# arduino_shield_drumline.net
KiCad netlist of a schematic drawn in EAGLE
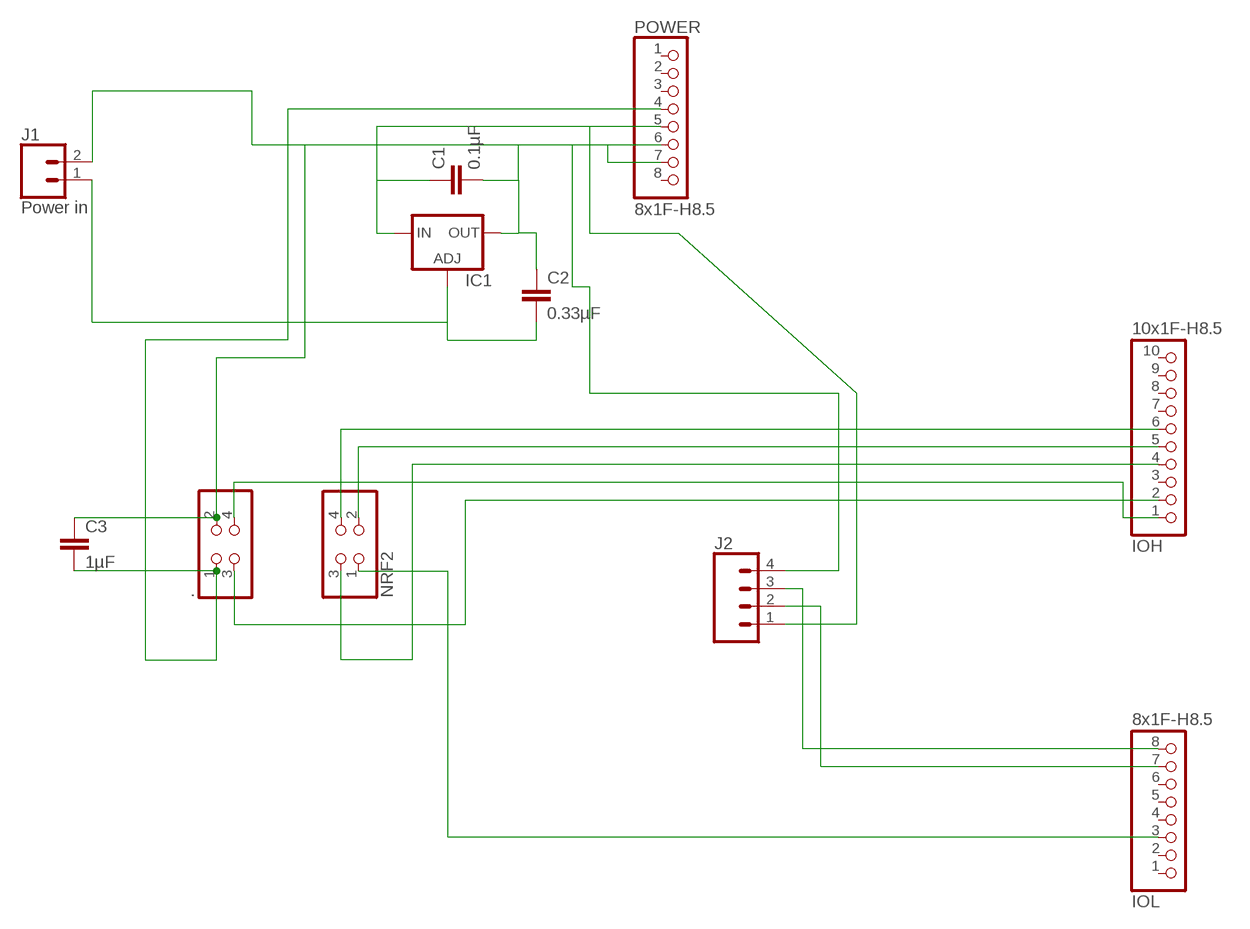
[diagram p0: schematic, sheet 1]

(export (version "E")
  (design (tool "Eeschema 10.0.6"))
  (components
    (comp (ref ".")
      (value "PINHD-2X2")
      (footprint "eagle-import:2X02")
      (libsource (lib "eagle-import") (part "PINHD-2X2"))
    )
    (comp (ref "C1")
      (value "0.1µF")
      (footprint "eagle-import:0805")
      (libsource (lib "eagle-import") (part "0.33UF/330NF-0805-50V-10%"))
    )
    (comp (ref "C2")
      (value "0.33µF")
      (footprint "eagle-import:0805")
      (libsource (lib "eagle-import") (part "0.33UF/330NF-0805-50V-10%"))
    )
    (comp (ref "C3")
      (value "1µF")
      (footprint "eagle-import:0805")
      (libsource (lib "eagle-import") (part "0.33UF/330NF-0805-50V-10%"))
    )
    (comp (ref "IC1")
      (value "LM138-TS")
      (footprint "eagle-import:TO220S")
      (libsource (lib "eagle-import") (part "LM138-TS"))
    )
    (comp (ref "IOH")
      (value "10x1F-H8.5")
      (footprint "eagle-import:1X10")
      (libsource (lib "eagle-import") (part "PINHD-1X10_ARD"))
    )
    (comp (ref "IOL")
      (value "8x1F-H8.5")
      (footprint "eagle-import:1X08")
      (libsource (lib "eagle-import") (part "PINHD-1X8"))
    )
    (comp (ref "J1")
      (value "Power in")
      (footprint "eagle-import:1X02")
      (libsource (lib "eagle-import") (part "CONN_02"))
    )
    (comp (ref "J2")
      (value "CONN_04")
      (footprint "eagle-import:1X04")
      (libsource (lib "eagle-import") (part "CONN_04"))
    )
    (comp (ref "NRF2")
      (value "PINHD-2X2")
      (footprint "eagle-import:2X02")
      (libsource (lib "eagle-import") (part "PINHD-2X2"))
    )
    (comp (ref "POWER")
      (value "8x1F-H8.5")
      (footprint "eagle-import:1X08")
      (libsource (lib "eagle-import") (part "PINHD-1X8"))
    )
  )
  (nets
    (net (code "1") (name "Net-(.-Pad1)") (class "Default")
      (node (ref ".") (pin "1") (pinfunction "1_1") (pintype "passive"))
      (node (ref "C3") (pin "2") (pinfunction "2_2") (pintype "passive"))
      (node (ref "POWER") (pin "4") (pinfunction "4_4") (pintype "passive"))
    )
    (net (code "2") (name "Net-(.-Pad3)") (class "Default")
      (node (ref ".") (pin "3") (pinfunction "3_3") (pintype "passive"))
      (node (ref "IOH") (pin "2") (pinfunction "2_2") (pintype "passive"))
    )
    (net (code "3") (name "Net-(.-Pad4)") (class "Default")
      (node (ref ".") (pin "4") (pinfunction "4_4") (pintype "passive"))
      (node (ref "IOH") (pin "1") (pinfunction "1_1") (pintype "passive"))
    )
    (net (code "4") (name "Net-(IC1-ADJ)") (class "Default")
      (node (ref "C2") (pin "2") (pinfunction "2_2") (pintype "passive"))
      (node (ref "IC1") (pin "1") (pinfunction "ADJ_1") (pintype "input"))
      (node (ref "J1") (pin "1") (pinfunction "1_1") (pintype "passive"))
    )
    (net (code "5") (name "Net-(IC1-IN)") (class "Default")
      (node (ref "C1") (pin "1") (pinfunction "1_1") (pintype "passive"))
      (node (ref "IC1") (pin "3") (pinfunction "IN_3") (pintype "input"))
      (node (ref "J2") (pin "1") (pinfunction "1_1") (pintype "passive"))
      (node (ref "POWER") (pin "5") (pinfunction "5_5") (pintype "passive"))
    )
    (net (code "6") (name "Net-(IC1-OUT)") (class "Default")
      (node (ref ".") (pin "2") (pinfunction "2_2") (pintype "passive"))
      (node (ref "C1") (pin "2") (pinfunction "2_2") (pintype "passive"))
      (node (ref "C2") (pin "1") (pinfunction "1_1") (pintype "passive"))
      (node (ref "C3") (pin "1") (pinfunction "1_1") (pintype "passive"))
      (node (ref "IC1") (pin "2") (pinfunction "OUT_2") (pintype "passive"))
      (node (ref "J1") (pin "2") (pinfunction "2_2") (pintype "passive"))
      (node (ref "J2") (pin "4") (pinfunction "4_4") (pintype "passive"))
      (node (ref "POWER") (pin "6") (pinfunction "6_6") (pintype "passive"))
      (node (ref "POWER") (pin "7") (pinfunction "7_7") (pintype "passive"))
    )
    (net (code "7") (name "Net-(IOH-Pad4)") (class "Default")
      (node (ref "IOH") (pin "4") (pinfunction "4_4") (pintype "passive"))
      (node (ref "NRF2") (pin "3") (pinfunction "3_3") (pintype "passive"))
    )
    (net (code "8") (name "Net-(IOH-Pad5)") (class "Default")
      (node (ref "IOH") (pin "5") (pinfunction "5_5") (pintype "passive"))
      (node (ref "NRF2") (pin "2") (pinfunction "2_2") (pintype "passive"))
    )
    (net (code "9") (name "Net-(IOH-Pad6)") (class "Default")
      (node (ref "IOH") (pin "6") (pinfunction "6_6") (pintype "passive"))
      (node (ref "NRF2") (pin "4") (pinfunction "4_4") (pintype "passive"))
    )
    (net (code "10") (name "Net-(IOL-Pad3)") (class "Default")
      (node (ref "IOL") (pin "3") (pinfunction "3_3") (pintype "passive"))
      (node (ref "NRF2") (pin "1") (pinfunction "1_1") (pintype "passive"))
    )
    (net (code "11") (name "Net-(IOL-Pad7)") (class "Default")
      (node (ref "IOL") (pin "7") (pinfunction "7_7") (pintype "passive"))
      (node (ref "J2") (pin "2") (pinfunction "2_2") (pintype "passive"))
    )
    (net (code "12") (name "Net-(IOL-Pad8)") (class "Default")
      (node (ref "IOL") (pin "8") (pinfunction "8_8") (pintype "passive"))
      (node (ref "J2") (pin "3") (pinfunction "3_3") (pintype "passive"))
    )
    (net (code "13") (name "unconnected-(IOH-Pad3)") (class "Default")
      (node (ref "IOH") (pin "3") (pinfunction "3_3") (pintype "passive"))
    )
    (net (code "14") (name "unconnected-(IOH-Pad7)") (class "Default")
      (node (ref "IOH") (pin "7") (pinfunction "7_7") (pintype "passive"))
    )
    (net (code "15") (name "unconnected-(IOH-Pad8)") (class "Default")
      (node (ref "IOH") (pin "8") (pinfunction "8_8") (pintype "passive"))
    )
    (net (code "16") (name "unconnected-(IOH-Pad9)") (class "Default")
      (node (ref "IOH") (pin "9") (pinfunction "9_9") (pintype "passive"))
    )
    (net (code "17") (name "unconnected-(IOH-Pad10)") (class "Default")
      (node (ref "IOH") (pin "10") (pinfunction "10_10") (pintype "passive"))
    )
    (net (code "18") (name "unconnected-(IOL-Pad1)") (class "Default")
      (node (ref "IOL") (pin "1") (pinfunction "1_1") (pintype "passive"))
    )
    (net (code "19") (name "unconnected-(IOL-Pad2)") (class "Default")
      (node (ref "IOL") (pin "2") (pinfunction "2_2") (pintype "passive"))
    )
    (net (code "20") (name "unconnected-(IOL-Pad4)") (class "Default")
      (node (ref "IOL") (pin "4") (pinfunction "4_4") (pintype "passive"))
    )
    (net (code "21") (name "unconnected-(IOL-Pad5)") (class "Default")
      (node (ref "IOL") (pin "5") (pinfunction "5_5") (pintype "passive"))
    )
    (net (code "22") (name "unconnected-(IOL-Pad6)") (class "Default")
      (node (ref "IOL") (pin "6") (pinfunction "6_6") (pintype "passive"))
    )
    (net (code "23") (name "unconnected-(POWER-Pad1)") (class "Default")
      (node (ref "POWER") (pin "1") (pinfunction "1_1") (pintype "passive"))
    )
    (net (code "24") (name "unconnected-(POWER-Pad2)") (class "Default")
      (node (ref "POWER") (pin "2") (pinfunction "2_2") (pintype "passive"))
    )
    (net (code "25") (name "unconnected-(POWER-Pad3)") (class "Default")
      (node (ref "POWER") (pin "3") (pinfunction "3_3") (pintype "passive"))
    )
    (net (code "26") (name "unconnected-(POWER-Pad8)") (class "Default")
      (node (ref "POWER") (pin "8") (pinfunction "8_8") (pintype "passive"))
    )
  )
)
